# SpiCurrent-New.net
KiCad netlist of a schematic drawn in EAGLE
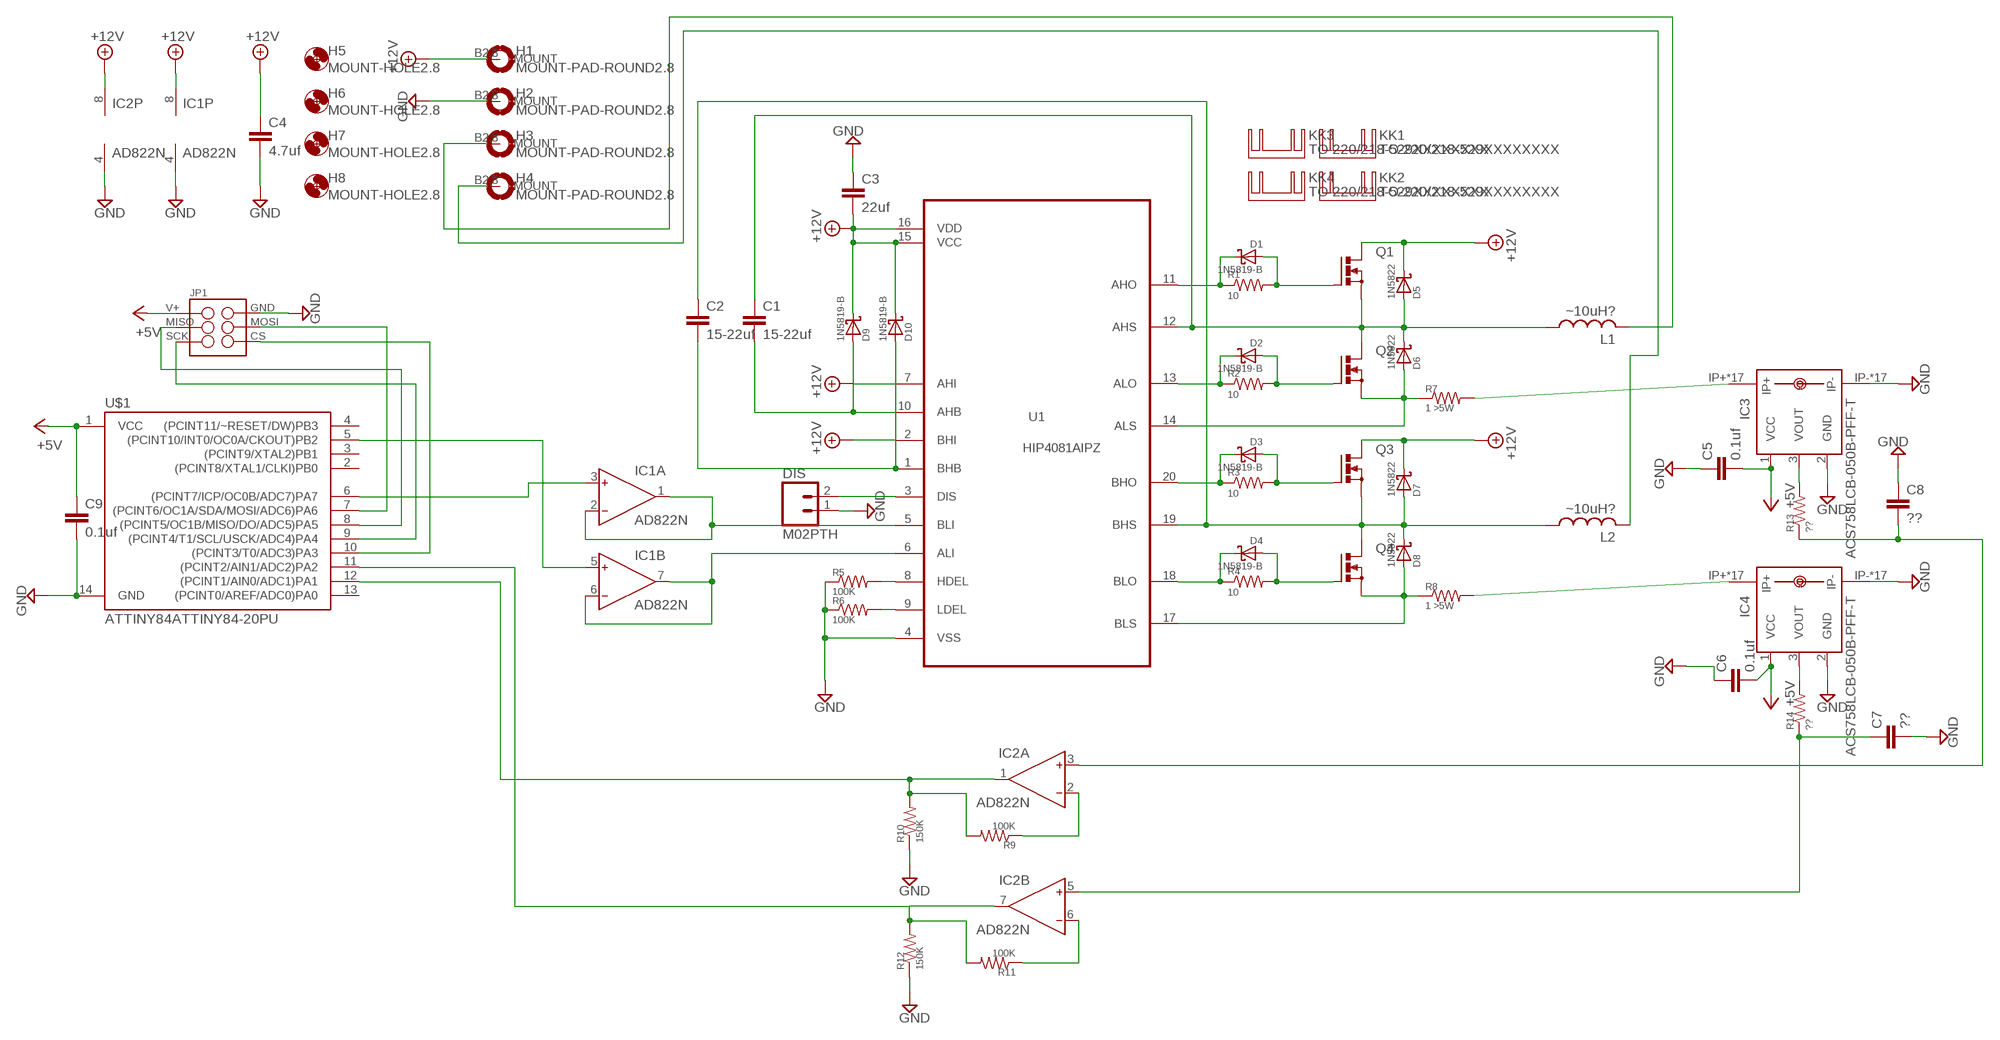
[diagram p0: schematic, sheet 1]

(export (version "E")
  (design (tool "Eeschema 10.0.6"))
  (components
    (comp (ref "C1")
      (value "15-22uf")
      (footprint "eagle-import:C050-055X075")
      (libsource (lib "eagle-import") (part "C-EU050-055X075"))
    )
    (comp (ref "C2")
      (value "15-22uf")
      (footprint "eagle-import:C050-055X075")
      (libsource (lib "eagle-import") (part "C-EU050-055X075"))
    )
    (comp (ref "C3")
      (value "22uf")
      (footprint "eagle-import:C050-055X075")
      (libsource (lib "eagle-import") (part "C-EU050-055X075"))
    )
    (comp (ref "C4")
      (value "4.7uf")
      (footprint "eagle-import:C050-055X075")
      (libsource (lib "eagle-import") (part "C-EU050-055X075"))
    )
    (comp (ref "C5")
      (value "0.1uf")
      (footprint "eagle-import:C050-055X075")
      (libsource (lib "eagle-import") (part "C-EU050-055X075"))
    )
    (comp (ref "C6")
      (value "0.1uf")
      (footprint "eagle-import:C050-055X075")
      (libsource (lib "eagle-import") (part "C-EU050-055X075"))
    )
    (comp (ref "C7")
      (value "??")
      (footprint "eagle-import:C050-055X075")
      (libsource (lib "eagle-import") (part "C-EU050-055X075"))
    )
    (comp (ref "C8")
      (value "??")
      (footprint "eagle-import:C050-055X075")
      (libsource (lib "eagle-import") (part "C-EU050-055X075"))
    )
    (comp (ref "C9")
      (value "0.1uf")
      (footprint "eagle-import:C050-055X075")
      (libsource (lib "eagle-import") (part "C-EU050-055X075"))
    )
    (comp (ref "D1")
      (value "1N5819-B")
      (footprint "eagle-import:DO41-7.6")
      (libsource (lib "eagle-import") (part "1N5819-B"))
    )
    (comp (ref "D2")
      (value "1N5819-B")
      (footprint "eagle-import:DO41-7.6")
      (libsource (lib "eagle-import") (part "1N5819-B"))
    )
    (comp (ref "D3")
      (value "1N5819-B")
      (footprint "eagle-import:DO41-7.6")
      (libsource (lib "eagle-import") (part "1N5819-B"))
    )
    (comp (ref "D4")
      (value "1N5819-B")
      (footprint "eagle-import:DO41-7.6")
      (libsource (lib "eagle-import") (part "1N5819-B"))
    )
    (comp (ref "D5")
      (value "1N5822")
      (footprint "eagle-import:DO41-7.6")
      (libsource (lib "eagle-import") (part "1N5819-B"))
    )
    (comp (ref "D6")
      (value "1N5822")
      (footprint "eagle-import:DO41-7.6")
      (libsource (lib "eagle-import") (part "1N5819-B"))
    )
    (comp (ref "D7")
      (value "1N5822")
      (footprint "eagle-import:DO41-7.6")
      (libsource (lib "eagle-import") (part "1N5819-B"))
    )
    (comp (ref "D8")
      (value "1N5822")
      (footprint "eagle-import:DO41-7.6")
      (libsource (lib "eagle-import") (part "1N5819-B"))
    )
    (comp (ref "D9")
      (value "1N5819-B")
      (footprint "eagle-import:DO41-7.6")
      (libsource (lib "eagle-import") (part "1N5819-B"))
    )
    (comp (ref "D10")
      (value "1N5819-B")
      (footprint "eagle-import:DO41-7.6")
      (libsource (lib "eagle-import") (part "1N5819-B"))
    )
    (comp (ref "DIS")
      (value "M02PTH")
      (footprint "eagle-import:1X02")
      (libsource (lib "eagle-import") (part "M02PTH"))
    )
    (comp (ref "H1")
      (value "MOUNT-PAD-ROUND2.8")
      (footprint "eagle-import:2,8-PAD")
      (libsource (lib "eagle-import") (part "MOUNT-PAD-ROUND2.8"))
    )
    (comp (ref "H2")
      (value "MOUNT-PAD-ROUND2.8")
      (footprint "eagle-import:2,8-PAD")
      (libsource (lib "eagle-import") (part "MOUNT-PAD-ROUND2.8"))
    )
    (comp (ref "H3")
      (value "MOUNT-PAD-ROUND2.8")
      (footprint "eagle-import:2,8-PAD")
      (libsource (lib "eagle-import") (part "MOUNT-PAD-ROUND2.8"))
    )
    (comp (ref "H4")
      (value "MOUNT-PAD-ROUND2.8")
      (footprint "eagle-import:2,8-PAD")
      (libsource (lib "eagle-import") (part "MOUNT-PAD-ROUND2.8"))
    )
    (comp (ref "H5")
      (value "MOUNT-HOLE2.8")
      (footprint "eagle-import:2,8")
      (libsource (lib "eagle-import") (part "MOUNT-HOLE2.8"))
    )
    (comp (ref "H6")
      (value "MOUNT-HOLE2.8")
      (footprint "eagle-import:2,8")
      (libsource (lib "eagle-import") (part "MOUNT-HOLE2.8"))
    )
    (comp (ref "H7")
      (value "MOUNT-HOLE2.8")
      (footprint "eagle-import:2,8")
      (libsource (lib "eagle-import") (part "MOUNT-HOLE2.8"))
    )
    (comp (ref "H8")
      (value "MOUNT-HOLE2.8")
      (footprint "eagle-import:2,8")
      (libsource (lib "eagle-import") (part "MOUNT-HOLE2.8"))
    )
    (comp (ref "IC1")
      (value "AD822N")
      (footprint "eagle-import:DIL08")
      (libsource (lib "eagle-import") (part "AD822N"))
    )
    (comp (ref "IC2")
      (value "AD822N")
      (footprint "eagle-import:DIL08")
      (libsource (lib "eagle-import") (part "AD822N"))
    )
    (comp (ref "IC3")
      (value "ACS758LCB-050B-PFF-T")
      (footprint "eagle-import:CB-PFF")
      (libsource (lib "eagle-import") (part "ACS758LCB-050B-PFF-T"))
    )
    (comp (ref "IC4")
      (value "ACS758LCB-050B-PFF-T")
      (footprint "eagle-import:CB-PFF")
      (libsource (lib "eagle-import") (part "ACS758LCB-050B-PFF-T"))
    )
    (comp (ref "JP1")
      (value "M03X2SHROUD")
      (footprint "eagle-import:2X3-SPI-SHROUDED")
      (libsource (lib "eagle-import") (part "M03X2SHROUD"))
    )
    (comp (ref "KK1")
      (value "TO-220/218-529XXXXXXXX")
      (footprint "eagle-import:529XXXXXXXX")
      (libsource (lib "eagle-import") (part "TO-220/218-529XXXXXXXX"))
    )
    (comp (ref "KK2")
      (value "TO-220/218-529XXXXXXXX")
      (footprint "eagle-import:529XXXXXXXX")
      (libsource (lib "eagle-import") (part "TO-220/218-529XXXXXXXX"))
    )
    (comp (ref "KK3")
      (value "TO-220/218-529XXXXXXXX")
      (footprint "eagle-import:529XXXXXXXX")
      (libsource (lib "eagle-import") (part "TO-220/218-529XXXXXXXX"))
    )
    (comp (ref "KK4")
      (value "TO-220/218-529XXXXXXXX")
      (footprint "eagle-import:529XXXXXXXX")
      (libsource (lib "eagle-import") (part "TO-220/218-529XXXXXXXX"))
    )
    (comp (ref "L1")
      (value "~10uH?")
      (footprint "eagle-import:TJ6-U2")
      (libsource (lib "eagle-import") (part "L-USTJ6-U2"))
    )
    (comp (ref "L2")
      (value "~10uH?")
      (footprint "eagle-import:TJ6-U2")
      (libsource (lib "eagle-import") (part "L-USTJ6-U2"))
    )
    (comp (ref "Q1")
      (value "PMOSFET_NTO220BV")
      (footprint "eagle-import:TO220BV")
      (libsource (lib "eagle-import") (part "PMOSFET_NTO220BV"))
    )
    (comp (ref "Q2")
      (value "PMOSFET_NTO220BV")
      (footprint "eagle-import:TO220BV")
      (libsource (lib "eagle-import") (part "PMOSFET_NTO220BV"))
    )
    (comp (ref "Q3")
      (value "PMOSFET_NTO220BV")
      (footprint "eagle-import:TO220BV")
      (libsource (lib "eagle-import") (part "PMOSFET_NTO220BV"))
    )
    (comp (ref "Q4")
      (value "PMOSFET_NTO220BV")
      (footprint "eagle-import:TO220BV")
      (libsource (lib "eagle-import") (part "PMOSFET_NTO220BV"))
    )
    (comp (ref "R1")
      (value "10")
      (footprint "eagle-import:0207_10")
      (libsource (lib "eagle-import") (part "R-US_0207/10"))
    )
    (comp (ref "R2")
      (value "10")
      (footprint "eagle-import:0207_10")
      (libsource (lib "eagle-import") (part "R-US_0207/10"))
    )
    (comp (ref "R3")
      (value "10")
      (footprint "eagle-import:0207_10")
      (libsource (lib "eagle-import") (part "R-US_0207/10"))
    )
    (comp (ref "R4")
      (value "10")
      (footprint "eagle-import:0207_10")
      (libsource (lib "eagle-import") (part "R-US_0207/10"))
    )
    (comp (ref "R5")
      (value "100K")
      (footprint "eagle-import:0207_10")
      (libsource (lib "eagle-import") (part "resistor-custom_R-US_0207/10"))
    )
    (comp (ref "R6")
      (value "100K")
      (footprint "eagle-import:0207_10")
      (libsource (lib "eagle-import") (part "resistor-custom_R-US_0207/10"))
    )
    (comp (ref "R7")
      (value "1 >5W")
      (footprint "eagle-import:VTA54")
      (libsource (lib "eagle-import") (part "resistor-custom_R-US_VTA54"))
    )
    (comp (ref "R8")
      (value "1 >5W")
      (footprint "eagle-import:VTA54")
      (libsource (lib "eagle-import") (part "resistor-custom_R-US_VTA54"))
    )
    (comp (ref "R9")
      (value "100K")
      (footprint "eagle-import:0207_10")
      (libsource (lib "eagle-import") (part "resistor-custom_R-US_0207/10"))
    )
    (comp (ref "R10")
      (value "150K")
      (footprint "eagle-import:0207_10")
      (libsource (lib "eagle-import") (part "resistor-custom_R-US_0207/10"))
    )
    (comp (ref "R11")
      (value "100K")
      (footprint "eagle-import:0207_10")
      (libsource (lib "eagle-import") (part "resistor-custom_R-US_0207/10"))
    )
    (comp (ref "R12")
      (value "150K")
      (footprint "eagle-import:0207_10")
      (libsource (lib "eagle-import") (part "resistor-custom_R-US_0207/10"))
    )
    (comp (ref "R13")
      (value "??")
      (footprint "eagle-import:0207_10")
      (libsource (lib "eagle-import") (part "resistor-custom_R-US_0207/10"))
    )
    (comp (ref "R14")
      (value "??")
      (footprint "eagle-import:0207_10")
      (libsource (lib "eagle-import") (part "resistor-custom_R-US_0207/10"))
    )
    (comp (ref "U$1")
      (value "ATTINY84ATTINY84-20PU")
      (footprint "eagle-import:DIL14")
      (libsource (lib "eagle-import") (part "ATTINY84ATTINY84-20PU"))
    )
    (comp (ref "U1")
      (value "HIP4081AIPZ")
      (footprint "eagle-import:DIP254P762X533-20")
      (libsource (lib "eagle-import") (part "HIP4081AIPZ"))
    )
  )
  (nets
    (net (code "1") (name "+5V") (class "Default")
      (node (ref "C5") (pin "2") (pinfunction "2_2") (pintype "passive"))
      (node (ref "C6") (pin "2") (pinfunction "2_2") (pintype "passive"))
      (node (ref "C9") (pin "1") (pinfunction "1_1") (pintype "passive"))
      (node (ref "IC3") (pin "1") (pinfunction "VCC_1") (pintype "power_in"))
      (node (ref "IC4") (pin "1") (pinfunction "VCC_1") (pintype "power_in"))
      (node (ref "JP1") (pin "1") (pinfunction "1_1") (pintype "bidirectional"))
      (node (ref "U$1") (pin "1") (pinfunction "VCC_1") (pintype "bidirectional"))
    )
    (net (code "2") (name "+12V") (class "Default")
      (node (ref "C3") (pin "2") (pinfunction "2_2") (pintype "passive"))
      (node (ref "C4") (pin "1") (pinfunction "1_1") (pintype "passive"))
      (node (ref "D10") (pin "C") (pinfunction "C_C") (pintype "passive"))
      (node (ref "D5") (pin "C") (pinfunction "C_C") (pintype "passive"))
      (node (ref "D7") (pin "C") (pinfunction "C_C") (pintype "passive"))
      (node (ref "D9") (pin "C") (pinfunction "C_C") (pintype "passive"))
      (node (ref "H1") (pin "B2,8") (pinfunction "MOUNT_B2,8") (pintype "passive"))
      (node (ref "IC1") (pin "8") (pinfunction "V+_8") (pintype "power_in"))
      (node (ref "IC2") (pin "8") (pinfunction "V+_8") (pintype "power_in"))
      (node (ref "Q1") (pin "D") (pinfunction "D_D") (pintype "passive"))
      (node (ref "Q3") (pin "D") (pinfunction "D_D") (pintype "passive"))
      (node (ref "U1") (pin "15") (pinfunction "VCC_15") (pintype "power_in"))
      (node (ref "U1") (pin "16") (pinfunction "VDD_16") (pintype "power_in"))
      (node (ref "U1") (pin "2") (pinfunction "BHI_2") (pintype "input"))
      (node (ref "U1") (pin "7") (pinfunction "AHI_7") (pintype "input"))
    )
    (net (code "3") (name "GND") (class "Default")
      (node (ref "C3") (pin "1") (pinfunction "1_1") (pintype "passive"))
      (node (ref "C4") (pin "2") (pinfunction "2_2") (pintype "passive"))
      (node (ref "C5") (pin "1") (pinfunction "1_1") (pintype "passive"))
      (node (ref "C6") (pin "1") (pinfunction "1_1") (pintype "passive"))
      (node (ref "C7") (pin "2") (pinfunction "2_2") (pintype "passive"))
      (node (ref "C8") (pin "1") (pinfunction "1_1") (pintype "passive"))
      (node (ref "C9") (pin "2") (pinfunction "2_2") (pintype "passive"))
      (node (ref "DIS") (pin "1") (pinfunction "1_1") (pintype "passive"))
      (node (ref "H2") (pin "B2,8") (pinfunction "MOUNT_B2,8") (pintype "passive"))
      (node (ref "IC1") (pin "4") (pinfunction "V-_4") (pintype "power_in"))
      (node (ref "IC2") (pin "4") (pinfunction "V-_4") (pintype "power_in"))
      (node (ref "IC3") (pin "2") (pinfunction "GND_2") (pintype "power_in"))
      (node (ref "IC3") (pin "IP-") (pinfunction "IP-_IP-") (pintype "passive"))
      (node (ref "IC3") (pin "IP-@10") (pinfunction "IP-_IP-@10") (pintype "passive"))
      (node (ref "IC3") (pin "IP-@11") (pinfunction "IP-_IP-@11") (pintype "passive"))
      (node (ref "IC3") (pin "IP-@12") (pinfunction "IP-_IP-@12") (pintype "passive"))
      (node (ref "IC3") (pin "IP-@13") (pinfunction "IP-_IP-@13") (pintype "passive"))
      (node (ref "IC3") (pin "IP-@14") (pinfunction "IP-_IP-@14") (pintype "passive"))
      (node (ref "IC3") (pin "IP-@15") (pinfunction "IP-_IP-@15") (pintype "passive"))
      (node (ref "IC3") (pin "IP-@16") (pinfunction "IP-_IP-@16") (pintype "passive"))
      (node (ref "IC3") (pin "IP-@17") (pinfunction "IP-_IP-@17") (pintype "passive"))
      (node (ref "IC3") (pin "IP-@2") (pinfunction "IP-_IP-@2") (pintype "passive"))
      (node (ref "IC3") (pin "IP-@3") (pinfunction "IP-_IP-@3") (pintype "passive"))
      (node (ref "IC3") (pin "IP-@4") (pinfunction "IP-_IP-@4") (pintype "passive"))
      (node (ref "IC3") (pin "IP-@5") (pinfunction "IP-_IP-@5") (pintype "passive"))
      (node (ref "IC3") (pin "IP-@6") (pinfunction "IP-_IP-@6") (pintype "passive"))
      (node (ref "IC3") (pin "IP-@7") (pinfunction "IP-_IP-@7") (pintype "passive"))
      (node (ref "IC3") (pin "IP-@8") (pinfunction "IP-_IP-@8") (pintype "passive"))
      (node (ref "IC3") (pin "IP-@9") (pinfunction "IP-_IP-@9") (pintype "passive"))
      (node (ref "IC4") (pin "2") (pinfunction "GND_2") (pintype "power_in"))
      (node (ref "IC4") (pin "IP-") (pinfunction "IP-_IP-") (pintype "passive"))
      (node (ref "IC4") (pin "IP-@10") (pinfunction "IP-_IP-@10") (pintype "passive"))
      (node (ref "IC4") (pin "IP-@11") (pinfunction "IP-_IP-@11") (pintype "passive"))
      (node (ref "IC4") (pin "IP-@12") (pinfunction "IP-_IP-@12") (pintype "passive"))
      (node (ref "IC4") (pin "IP-@13") (pinfunction "IP-_IP-@13") (pintype "passive"))
      (node (ref "IC4") (pin "IP-@14") (pinfunction "IP-_IP-@14") (pintype "passive"))
      (node (ref "IC4") (pin "IP-@15") (pinfunction "IP-_IP-@15") (pintype "passive"))
      (node (ref "IC4") (pin "IP-@16") (pinfunction "IP-_IP-@16") (pintype "passive"))
      (node (ref "IC4") (pin "IP-@17") (pinfunction "IP-_IP-@17") (pintype "passive"))
      (node (ref "IC4") (pin "IP-@2") (pinfunction "IP-_IP-@2") (pintype "passive"))
      (node (ref "IC4") (pin "IP-@3") (pinfunction "IP-_IP-@3") (pintype "passive"))
      (node (ref "IC4") (pin "IP-@4") (pinfunction "IP-_IP-@4") (pintype "passive"))
      (node (ref "IC4") (pin "IP-@5") (pinfunction "IP-_IP-@5") (pintype "passive"))
      (node (ref "IC4") (pin "IP-@6") (pinfunction "IP-_IP-@6") (pintype "passive"))
      (node (ref "IC4") (pin "IP-@7") (pinfunction "IP-_IP-@7") (pintype "passive"))
      (node (ref "IC4") (pin "IP-@8") (pinfunction "IP-_IP-@8") (pintype "passive"))
      (node (ref "IC4") (pin "IP-@9") (pinfunction "IP-_IP-@9") (pintype "passive"))
      (node (ref "JP1") (pin "2") (pinfunction "2_2") (pintype "bidirectional"))
      (node (ref "R10") (pin "1") (pinfunction "1_1") (pintype "passive"))
      (node (ref "R12") (pin "1") (pinfunction "1_1") (pintype "passive"))
      (node (ref "R5") (pin "1") (pinfunction "1_1") (pintype "passive"))
      (node (ref "R6") (pin "1") (pinfunction "1_1") (pintype "passive"))
      (node (ref "U$1") (pin "14") (pinfunction "GND_14") (pintype "bidirectional"))
      (node (ref "U1") (pin "4") (pinfunction "VSS_4") (pintype "power_in"))
    )
    (net (code "4") (name "Net-(D1-PadA)") (class "Default")
      (node (ref "D1") (pin "A") (pinfunction "A_A") (pintype "passive"))
      (node (ref "Q1") (pin "G") (pinfunction "G_G") (pintype "passive"))
      (node (ref "R1") (pin "2") (pinfunction "2_2") (pintype "passive"))
    )
    (net (code "5") (name "Net-(D2-PadA)") (class "Default")
      (node (ref "D2") (pin "A") (pinfunction "A_A") (pintype "passive"))
      (node (ref "Q2") (pin "G") (pinfunction "G_G") (pintype "passive"))
      (node (ref "R2") (pin "2") (pinfunction "2_2") (pintype "passive"))
    )
    (net (code "6") (name "Net-(D3-PadA)") (class "Default")
      (node (ref "D3") (pin "A") (pinfunction "A_A") (pintype "passive"))
      (node (ref "Q3") (pin "G") (pinfunction "G_G") (pintype "passive"))
      (node (ref "R3") (pin "2") (pinfunction "2_2") (pintype "passive"))
    )
    (net (code "7") (name "Net-(D4-PadA)") (class "Default")
      (node (ref "D4") (pin "A") (pinfunction "A_A") (pintype "passive"))
      (node (ref "Q4") (pin "G") (pinfunction "G_G") (pintype "passive"))
      (node (ref "R4") (pin "2") (pinfunction "2_2") (pintype "passive"))
    )
    (net (code "8") (name "Net-(H3-MOUNT)") (class "Default")
      (node (ref "H3") (pin "B2,8") (pinfunction "MOUNT_B2,8") (pintype "passive"))
      (node (ref "L1") (pin "2") (pinfunction "2_2") (pintype "passive"))
    )
    (net (code "9") (name "Net-(H4-MOUNT)") (class "Default")
      (node (ref "H4") (pin "B2,8") (pinfunction "MOUNT_B2,8") (pintype "passive"))
      (node (ref "L2") (pin "2") (pinfunction "2_2") (pintype "passive"))
    )
    (net (code "10") (name "Net-(IC1A-IN+)") (class "Default")
      (node (ref "IC1") (pin "3") (pinfunction "IN+_3") (pintype "input"))
      (node (ref "U$1") (pin "6") (pinfunction "(PCINT7/ICP/OC0B/ADC7)PA7_6") (pintype "bidirectional"))
    )
    (net (code "11") (name "Net-(IC1A-IN-)") (class "Default")
      (node (ref "IC1") (pin "1") (pinfunction "OUT_1") (pintype "output"))
      (node (ref "IC1") (pin "2") (pinfunction "IN-_2") (pintype "input"))
      (node (ref "U1") (pin "5") (pinfunction "BLI_5") (pintype "input"))
    )
    (net (code "12") (name "Net-(IC1B-IN+)") (class "Default")
      (node (ref "IC1") (pin "5") (pinfunction "IN+_5") (pintype "input"))
      (node (ref "U$1") (pin "5") (pinfunction "(PCINT10/INT0/OC0A/CKOUT)PB2_5") (pintype "bidirectional"))
    )
    (net (code "13") (name "Net-(IC1B-IN-)") (class "Default")
      (node (ref "IC1") (pin "6") (pinfunction "IN-_6") (pintype "input"))
      (node (ref "IC1") (pin "7") (pinfunction "OUT_7") (pintype "output"))
      (node (ref "U1") (pin "6") (pinfunction "ALI_6") (pintype "input"))
    )
    (net (code "14") (name "Net-(IC2A-IN+)") (class "Default")
      (node (ref "C8") (pin "2") (pinfunction "2_2") (pintype "passive"))
      (node (ref "IC2") (pin "3") (pinfunction "IN+_3") (pintype "input"))
      (node (ref "R13") (pin "1") (pinfunction "1_1") (pintype "passive"))
    )
    (net (code "15") (name "Net-(IC2A-IN-)") (class "Default")
      (node (ref "IC2") (pin "2") (pinfunction "IN-_2") (pintype "input"))
      (node (ref "R9") (pin "1") (pinfunction "1_1") (pintype "passive"))
    )
    (net (code "16") (name "Net-(IC2A-OUT)") (class "Default")
      (node (ref "IC2") (pin "1") (pinfunction "OUT_1") (pintype "output"))
      (node (ref "R10") (pin "2") (pinfunction "2_2") (pintype "passive"))
      (node (ref "R9") (pin "2") (pinfunction "2_2") (pintype "passive"))
      (node (ref "U$1") (pin "12") (pinfunction "(PCINT1/AIN0/ADC1)PA1_12") (pintype "bidirectional"))
    )
    (net (code "17") (name "Net-(IC2B-IN+)") (class "Default")
      (node (ref "C7") (pin "1") (pinfunction "1_1") (pintype "passive"))
      (node (ref "IC2") (pin "5") (pinfunction "IN+_5") (pintype "input"))
      (node (ref "R14") (pin "1") (pinfunction "1_1") (pintype "passive"))
    )
    (net (code "18") (name "Net-(IC2B-IN-)") (class "Default")
      (node (ref "IC2") (pin "6") (pinfunction "IN-_6") (pintype "input"))
      (node (ref "R11") (pin "1") (pinfunction "1_1") (pintype "passive"))
    )
    (net (code "19") (name "Net-(IC2B-OUT)") (class "Default")
      (node (ref "IC2") (pin "7") (pinfunction "OUT_7") (pintype "output"))
      (node (ref "R11") (pin "2") (pinfunction "2_2") (pintype "passive"))
      (node (ref "R12") (pin "2") (pinfunction "2_2") (pintype "passive"))
      (node (ref "U$1") (pin "11") (pinfunction "(PCINT2/AIN1/ADC2)PA2_11") (pintype "bidirectional"))
    )
    (net (code "20") (name "Net-(IC3-IP+-PadIP+@10)") (class "Default")
      (node (ref "IC3") (pin "IP+") (pinfunction "IP+_IP+") (pintype "passive"))
      (node (ref "IC3") (pin "IP+@10") (pinfunction "IP+_IP+@10") (pintype "passive"))
      (node (ref "IC3") (pin "IP+@11") (pinfunction "IP+_IP+@11") (pintype "passive"))
      (node (ref "IC3") (pin "IP+@12") (pinfunction "IP+_IP+@12") (pintype "passive"))
      (node (ref "IC3") (pin "IP+@13") (pinfunction "IP+_IP+@13") (pintype "passive"))
      (node (ref "IC3") (pin "IP+@14") (pinfunction "IP+_IP+@14") (pintype "passive"))
      (node (ref "IC3") (pin "IP+@15") (pinfunction "IP+_IP+@15") (pintype "passive"))
      (node (ref "IC3") (pin "IP+@16") (pinfunction "IP+_IP+@16") (pintype "passive"))
      (node (ref "IC3") (pin "IP+@17") (pinfunction "IP+_IP+@17") (pintype "passive"))
      (node (ref "IC3") (pin "IP+@2") (pinfunction "IP+_IP+@2") (pintype "passive"))
      (node (ref "IC3") (pin "IP+@3") (pinfunction "IP+_IP+@3") (pintype "passive"))
      (node (ref "IC3") (pin "IP+@4") (pinfunction "IP+_IP+@4") (pintype "passive"))
      (node (ref "IC3") (pin "IP+@5") (pinfunction "IP+_IP+@5") (pintype "passive"))
      (node (ref "IC3") (pin "IP+@6") (pinfunction "IP+_IP+@6") (pintype "passive"))
      (node (ref "IC3") (pin "IP+@7") (pinfunction "IP+_IP+@7") (pintype "passive"))
      (node (ref "IC3") (pin "IP+@8") (pinfunction "IP+_IP+@8") (pintype "passive"))
      (node (ref "IC3") (pin "IP+@9") (pinfunction "IP+_IP+@9") (pintype "passive"))
      (node (ref "R7") (pin "2") (pinfunction "2_2") (pintype "passive"))
    )
    (net (code "21") (name "Net-(IC3-VOUT)") (class "Default")
      (node (ref "IC3") (pin "3") (pinfunction "VOUT_3") (pintype "output"))
      (node (ref "R13") (pin "2") (pinfunction "2_2") (pintype "passive"))
    )
    (net (code "22") (name "Net-(IC4-IP+-PadIP+@10)") (class "Default")
      (node (ref "IC4") (pin "IP+") (pinfunction "IP+_IP+") (pintype "passive"))
      (node (ref "IC4") (pin "IP+@10") (pinfunction "IP+_IP+@10") (pintype "passive"))
      (node (ref "IC4") (pin "IP+@11") (pinfunction "IP+_IP+@11") (pintype "passive"))
      (node (ref "IC4") (pin "IP+@12") (pinfunction "IP+_IP+@12") (pintype "passive"))
      (node (ref "IC4") (pin "IP+@13") (pinfunction "IP+_IP+@13") (pintype "passive"))
      (node (ref "IC4") (pin "IP+@14") (pinfunction "IP+_IP+@14") (pintype "passive"))
      (node (ref "IC4") (pin "IP+@15") (pinfunction "IP+_IP+@15") (pintype "passive"))
      (node (ref "IC4") (pin "IP+@16") (pinfunction "IP+_IP+@16") (pintype "passive"))
      (node (ref "IC4") (pin "IP+@17") (pinfunction "IP+_IP+@17") (pintype "passive"))
      (node (ref "IC4") (pin "IP+@2") (pinfunction "IP+_IP+@2") (pintype "passive"))
      (node (ref "IC4") (pin "IP+@3") (pinfunction "IP+_IP+@3") (pintype "passive"))
      (node (ref "IC4") (pin "IP+@4") (pinfunction "IP+_IP+@4") (pintype "passive"))
      (node (ref "IC4") (pin "IP+@5") (pinfunction "IP+_IP+@5") (pintype "passive"))
      (node (ref "IC4") (pin "IP+@6") (pinfunction "IP+_IP+@6") (pintype "passive"))
      (node (ref "IC4") (pin "IP+@7") (pinfunction "IP+_IP+@7") (pintype "passive"))
      (node (ref "IC4") (pin "IP+@8") (pinfunction "IP+_IP+@8") (pintype "passive"))
      (node (ref "IC4") (pin "IP+@9") (pinfunction "IP+_IP+@9") (pintype "passive"))
      (node (ref "R8") (pin "2") (pinfunction "2_2") (pintype "passive"))
    )
    (net (code "23") (name "Net-(IC4-VOUT)") (class "Default")
      (node (ref "IC4") (pin "3") (pinfunction "VOUT_3") (pintype "output"))
      (node (ref "R14") (pin "2") (pinfunction "2_2") (pintype "passive"))
    )
    (net (code "24") (name "Net-(U$1-(PCINT3{slash}T0{slash}ADC3)PA3)") (class "Default")
      (node (ref "JP1") (pin "6") (pinfunction "6_6") (pintype "bidirectional"))
      (node (ref "U$1") (pin "10") (pinfunction "(PCINT3/T0/ADC3)PA3_10") (pintype "bidirectional"))
    )
    (net (code "25") (name "Net-(U$1-(PCINT4{slash}T1{slash}SCL{slash}USCK{slash}ADC4)PA4)") (class "Default")
      (node (ref "JP1") (pin "5") (pinfunction "5_5") (pintype "bidirectional"))
      (node (ref "U$1") (pin "9") (pinfunction "(PCINT4/T1/SCL/USCK/ADC4)PA4_9") (pintype "bidirectional"))
    )
    (net (code "26") (name "Net-(U$1-(PCINT5{slash}OC1B{slash}MISO{slash}DO{slash}ADC5)PA5)") (class "Default")
      (node (ref "JP1") (pin "3") (pinfunction "3_3") (pintype "bidirectional"))
      (node (ref "U$1") (pin "8") (pinfunction "(PCINT5/OC1B/MISO/DO/ADC5)PA5_8") (pintype "bidirectional"))
    )
    (net (code "27") (name "Net-(U$1-(PCINT6{slash}OC1A{slash}SDA{slash}MOSI{slash}ADC6)PA6)") (class "Default")
      (node (ref "JP1") (pin "4") (pinfunction "4_4") (pintype "bidirectional"))
      (node (ref "U$1") (pin "7") (pinfunction "(PCINT6/OC1A/SDA/MOSI/ADC6)PA6_7") (pintype "bidirectional"))
    )
    (net (code "28") (name "Net-(U1-AHB)") (class "Default")
      (node (ref "C1") (pin "2") (pinfunction "2_2") (pintype "passive"))
      (node (ref "D9") (pin "A") (pinfunction "A_A") (pintype "passive"))
      (node (ref "U1") (pin "10") (pinfunction "AHB_10") (pintype "input"))
    )
    (net (code "29") (name "Net-(U1-AHO)") (class "Default")
      (node (ref "D1") (pin "C") (pinfunction "C_C") (pintype "passive"))
      (node (ref "R1") (pin "1") (pinfunction "1_1") (pintype "passive"))
      (node (ref "U1") (pin "11") (pinfunction "AHO_11") (pintype "output"))
    )
    (net (code "30") (name "Net-(U1-AHS)") (class "Default")
      (node (ref "C1") (pin "1") (pinfunction "1_1") (pintype "passive"))
      (node (ref "D5") (pin "A") (pinfunction "A_A") (pintype "passive"))
      (node (ref "D6") (pin "C") (pinfunction "C_C") (pintype "passive"))
      (node (ref "L1") (pin "1") (pinfunction "1_1") (pintype "passive"))
      (node (ref "Q1") (pin "S") (pinfunction "S_S") (pintype "passive"))
      (node (ref "Q2") (pin "D") (pinfunction "D_D") (pintype "passive"))
      (node (ref "U1") (pin "12") (pinfunction "AHS_12") (pintype "passive"))
    )
    (net (code "31") (name "Net-(U1-ALO)") (class "Default")
      (node (ref "D2") (pin "C") (pinfunction "C_C") (pintype "passive"))
      (node (ref "R2") (pin "1") (pinfunction "1_1") (pintype "passive"))
      (node (ref "U1") (pin "13") (pinfunction "ALO_13") (pintype "output"))
    )
    (net (code "32") (name "Net-(U1-ALS)") (class "Default")
      (node (ref "D6") (pin "A") (pinfunction "A_A") (pintype "passive"))
      (node (ref "Q2") (pin "S") (pinfunction "S_S") (pintype "passive"))
      (node (ref "R7") (pin "1") (pinfunction "1_1") (pintype "passive"))
      (node (ref "U1") (pin "14") (pinfunction "ALS_14") (pintype "passive"))
    )
    (net (code "33") (name "Net-(U1-BHB)") (class "Default")
      (node (ref "C2") (pin "2") (pinfunction "2_2") (pintype "passive"))
      (node (ref "D10") (pin "A") (pinfunction "A_A") (pintype "passive"))
      (node (ref "U1") (pin "1") (pinfunction "BHB_1") (pintype "input"))
    )
    (net (code "34") (name "Net-(U1-BHO)") (class "Default")
      (node (ref "D3") (pin "C") (pinfunction "C_C") (pintype "passive"))
      (node (ref "R3") (pin "1") (pinfunction "1_1") (pintype "passive"))
      (node (ref "U1") (pin "20") (pinfunction "BHO_20") (pintype "output"))
    )
    (net (code "35") (name "Net-(U1-BHS)") (class "Default")
      (node (ref "C2") (pin "1") (pinfunction "1_1") (pintype "passive"))
      (node (ref "D7") (pin "A") (pinfunction "A_A") (pintype "passive"))
      (node (ref "D8") (pin "C") (pinfunction "C_C") (pintype "passive"))
      (node (ref "L2") (pin "1") (pinfunction "1_1") (pintype "passive"))
      (node (ref "Q3") (pin "S") (pinfunction "S_S") (pintype "passive"))
      (node (ref "Q4") (pin "D") (pinfunction "D_D") (pintype "passive"))
      (node (ref "U1") (pin "19") (pinfunction "BHS_19") (pintype "passive"))
    )
    (net (code "36") (name "Net-(U1-BLO)") (class "Default")
      (node (ref "D4") (pin "C") (pinfunction "C_C") (pintype "passive"))
      (node (ref "R4") (pin "1") (pinfunction "1_1") (pintype "passive"))
      (node (ref "U1") (pin "18") (pinfunction "BLO_18") (pintype "output"))
    )
    (net (code "37") (name "Net-(U1-BLS)") (class "Default")
      (node (ref "D8") (pin "A") (pinfunction "A_A") (pintype "passive"))
      (node (ref "Q4") (pin "S") (pinfunction "S_S") (pintype "passive"))
      (node (ref "R8") (pin "1") (pinfunction "1_1") (pintype "passive"))
      (node (ref "U1") (pin "17") (pinfunction "BLS_17") (pintype "passive"))
    )
    (net (code "38") (name "Net-(U1-DIS)") (class "Default")
      (node (ref "DIS") (pin "2") (pinfunction "2_2") (pintype "passive"))
      (node (ref "U1") (pin "3") (pinfunction "DIS_3") (pintype "input"))
    )
    (net (code "39") (name "Net-(U1-HDEL)") (class "Default")
      (node (ref "R5") (pin "2") (pinfunction "2_2") (pintype "passive"))
      (node (ref "U1") (pin "8") (pinfunction "HDEL_8") (pintype "input"))
    )
    (net (code "40") (name "Net-(U1-LDEL)") (class "Default")
      (node (ref "R6") (pin "2") (pinfunction "2_2") (pintype "passive"))
      (node (ref "U1") (pin "9") (pinfunction "LDEL_9") (pintype "input"))
    )
    (net (code "41") (name "unconnected-(U$1-(PCINT0{slash}AREF{slash}ADC0)PA0-Pad13)") (class "Default")
      (node (ref "U$1") (pin "13") (pinfunction "(PCINT0/AREF/ADC0)PA0_13") (pintype "bidirectional"))
    )
    (net (code "42") (name "unconnected-(U$1-(PCINT8{slash}XTAL1{slash}CLKI)PB0-Pad2)") (class "Default")
      (node (ref "U$1") (pin "2") (pinfunction "(PCINT8/XTAL1/CLKI)PB0_2") (pintype "bidirectional"))
    )
    (net (code "43") (name "unconnected-(U$1-(PCINT9{slash}XTAL2)PB1-Pad3)") (class "Default")
      (node (ref "U$1") (pin "3") (pinfunction "(PCINT9/XTAL2)PB1_3") (pintype "bidirectional"))
    )
    (net (code "44") (name "unconnected-(U$1-(PCINT11{slash}~{RESET{slash}DW})PB3-Pad4)") (class "Default")
      (node (ref "U$1") (pin "4") (pinfunction "(PCINT11/~{RESET/DW})PB3_4") (pintype "bidirectional"))
    )
  )
)
